# UV_Sterlizer_2.net
KiCad netlist of a schematic drawn in EAGLE
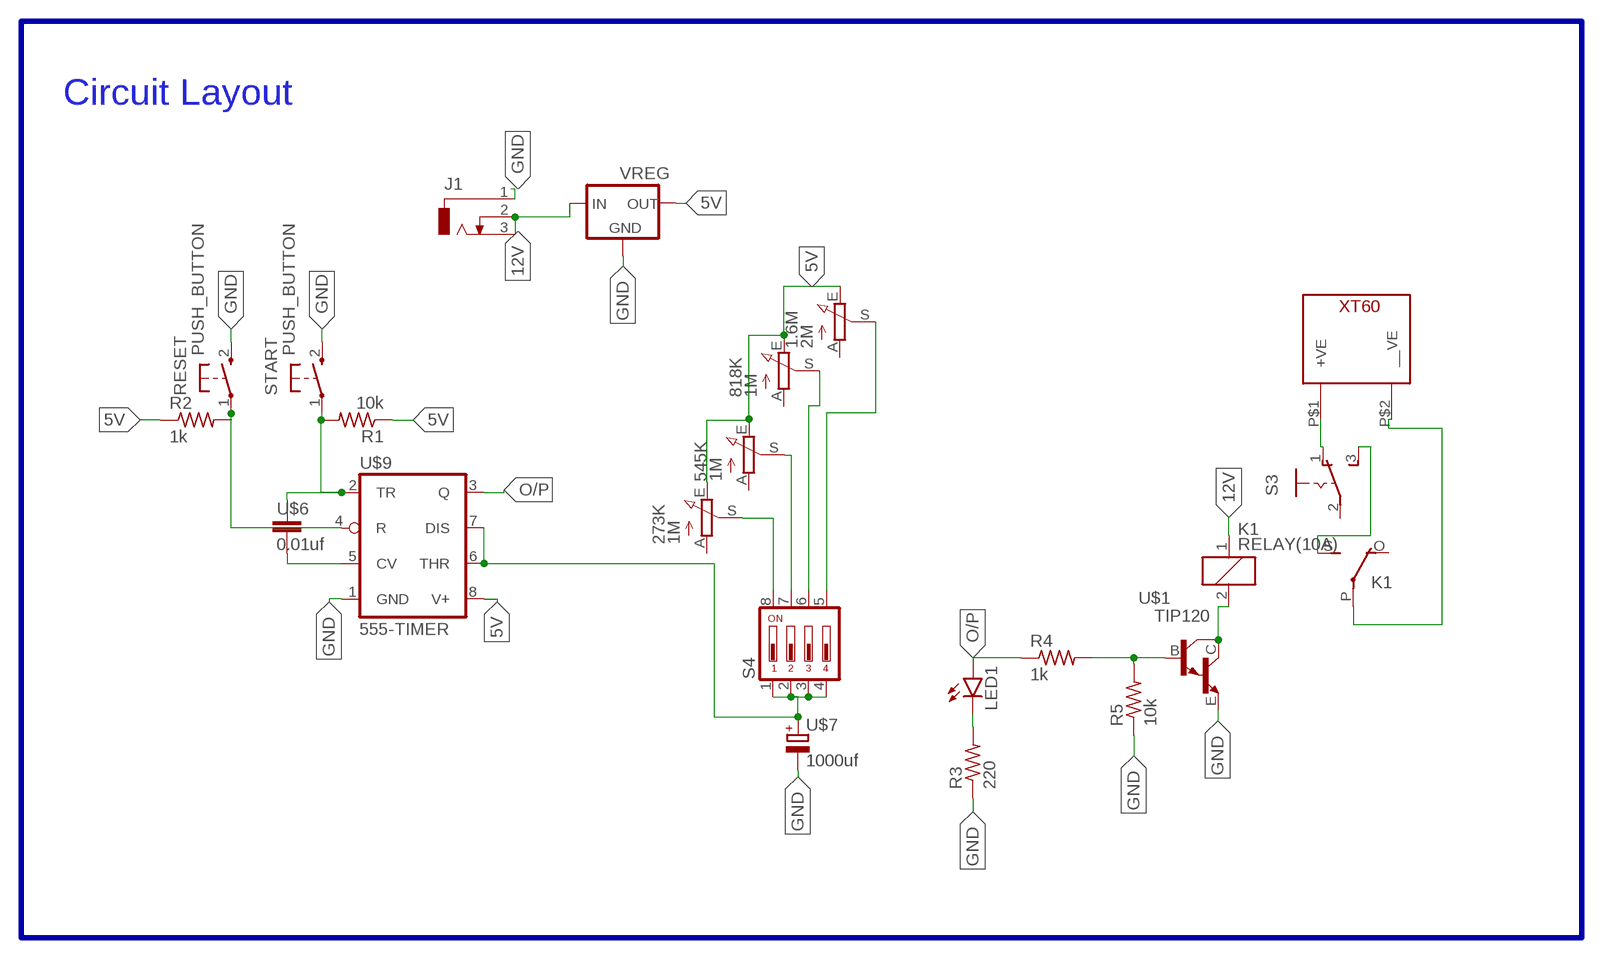
[diagram p0: schematic, sheet 1]

(export (version "E")
  (design (tool "Eeschema 10.0.6"))
  (components
    (comp (ref "1.6M")
      (value "2M")
      (footprint "eagle-import:RJ9W")
      (libsource (lib "eagle-import") (part "TRIMMER"))
    )
    (comp (ref "273K")
      (value "1M")
      (footprint "eagle-import:RJ9W")
      (libsource (lib "eagle-import") (part "TRIMMER"))
    )
    (comp (ref "545K")
      (value "1M")
      (footprint "eagle-import:RJ9W")
      (libsource (lib "eagle-import") (part "TRIMMER"))
    )
    (comp (ref "818K")
      (value "1M")
      (footprint "eagle-import:RJ9W")
      (libsource (lib "eagle-import") (part "TRIMMER"))
    )
    (comp (ref "J1")
      (value "DCJ0303")
      (footprint "eagle-import:DCJ0303")
      (libsource (lib "eagle-import") (part "DCJ0303"))
    )
    (comp (ref "K1")
      (value "RELAY(10A)")
      (footprint "eagle-import:G5LE")
      (libsource (lib "eagle-import") (part "RELAY(10A)"))
    )
    (comp (ref "LED1")
      (value "LED5MM")
      (footprint "eagle-import:LED5MM")
      (libsource (lib "eagle-import") (part "LED5MM"))
    )
    (comp (ref "R1")
      (value "10k")
      (footprint "eagle-import:0204_7")
      (libsource (lib "eagle-import") (part "R-US_0204/7"))
    )
    (comp (ref "R2")
      (value "1k")
      (footprint "eagle-import:0204_7")
      (libsource (lib "eagle-import") (part "R-US_0204/7"))
    )
    (comp (ref "R3")
      (value "220")
      (footprint "eagle-import:0204_7")
      (libsource (lib "eagle-import") (part "R-US_0204/7"))
    )
    (comp (ref "R4")
      (value "1k")
      (footprint "eagle-import:0204_7")
      (libsource (lib "eagle-import") (part "R-US_0204/7"))
    )
    (comp (ref "R5")
      (value "10k")
      (footprint "eagle-import:0204_7")
      (libsource (lib "eagle-import") (part "R-US_0204/7"))
    )
    (comp (ref "RESET")
      (value "PUSH_BUTTON")
      (footprint "eagle-import:B3F-10XX")
      (libsource (lib "eagle-import") (part "PUSH_BUTTON"))
    )
    (comp (ref "S3")
      (value "SLIDING_SWITCH")
      (footprint "eagle-import:255SB")
      (libsource (lib "eagle-import") (part "SLIDING_SWITCH"))
    )
    (comp (ref "S4")
      (value "DS04")
      (footprint "eagle-import:DS-04")
      (libsource (lib "eagle-import") (part "DS04"))
    )
    (comp (ref "START")
      (value "PUSH_BUTTON")
      (footprint "eagle-import:B3F-10XX")
      (libsource (lib "eagle-import") (part "PUSH_BUTTON"))
    )
    (comp (ref "U$1")
      (value "TIP120")
      (footprint "eagle-import:TIP120")
      (libsource (lib "eagle-import") (part "TIP120"))
    )
    (comp (ref "U$6")
      (value "0.01uf")
      (footprint "eagle-import:C025-025X050")
      (libsource (lib "eagle-import") (part "CAPACITOR"))
    )
    (comp (ref "U$7")
      (value "1000uf")
      (footprint "eagle-import:E3,5-8")
      (libsource (lib "eagle-import") (part "CAP_POL"))
    )
    (comp (ref "U$8")
      (value "XT60_CONNECTOR")
      (footprint "eagle-import:XT60")
      (libsource (lib "eagle-import") (part "XT60_CONNECTOR"))
    )
    (comp (ref "U$9")
      (value "555-TIMER")
      (footprint "eagle-import:DIL08")
      (libsource (lib "eagle-import") (part "555-TIMER"))
    )
    (comp (ref "VREG")
      (value "78XX-METAL")
      (footprint "eagle-import:TO3-79")
      (libsource (lib "eagle-import") (part "78XX-METAL"))
    )
  )
  (nets
    (net (code "1") (name "5V") (class "Default")
      (node (ref "1.6M") (pin "E") (pinfunction "E_E") (pintype "passive"))
      (node (ref "273K") (pin "E") (pinfunction "E_E") (pintype "passive"))
      (node (ref "545K") (pin "E") (pinfunction "E_E") (pintype "passive"))
      (node (ref "818K") (pin "E") (pinfunction "E_E") (pintype "passive"))
      (node (ref "R1") (pin "1") (pinfunction "1_1") (pintype "passive"))
      (node (ref "R2") (pin "1") (pinfunction "1_1") (pintype "passive"))
      (node (ref "U$9") (pin "8") (pinfunction "V+_8") (pintype "power_in"))
      (node (ref "VREG") (pin "1") (pinfunction "OUT_1") (pintype "passive"))
    )
    (net (code "2") (name "12V") (class "Default")
      (node (ref "J1") (pin "2") (pinfunction "2_2") (pintype "passive"))
      (node (ref "J1") (pin "3") (pinfunction "3_3") (pintype "passive"))
      (node (ref "K1") (pin "1") (pinfunction "1_1") (pintype "passive"))
      (node (ref "VREG") (pin "3") (pinfunction "IN_3") (pintype "input"))
    )
    (net (code "3") (name "GND") (class "Default")
      (node (ref "J1") (pin "1") (pinfunction "1_1") (pintype "passive"))
      (node (ref "R3") (pin "1") (pinfunction "1_1") (pintype "passive"))
      (node (ref "R5") (pin "1") (pinfunction "1_1") (pintype "passive"))
      (node (ref "RESET") (pin "2") (pinfunction "S_2") (pintype "passive"))
      (node (ref "START") (pin "2") (pinfunction "S_2") (pintype "passive"))
      (node (ref "U$1") (pin "E") (pinfunction "E_E") (pintype "passive"))
      (node (ref "U$7") (pin "-") (pinfunction "-_-") (pintype "passive"))
      (node (ref "U$9") (pin "1") (pinfunction "GND_1") (pintype "power_in"))
      (node (ref "VREG") (pin "2") (pinfunction "GND_2") (pintype "input"))
    )
    (net (code "4") (name "Net-(1.6M-PadS)") (class "Default")
      (node (ref "1.6M") (pin "S") (pinfunction "S_S") (pintype "passive"))
      (node (ref "S4") (pin "5") (pinfunction "5_5") (pintype "passive"))
    )
    (net (code "5") (name "Net-(273K-PadS)") (class "Default")
      (node (ref "273K") (pin "S") (pinfunction "S_S") (pintype "passive"))
      (node (ref "S4") (pin "8") (pinfunction "8_8") (pintype "passive"))
    )
    (net (code "6") (name "Net-(545K-PadS)") (class "Default")
      (node (ref "545K") (pin "S") (pinfunction "S_S") (pintype "passive"))
      (node (ref "S4") (pin "7") (pinfunction "7_7") (pintype "passive"))
    )
    (net (code "7") (name "Net-(818K-PadS)") (class "Default")
      (node (ref "818K") (pin "S") (pinfunction "S_S") (pintype "passive"))
      (node (ref "S4") (pin "6") (pinfunction "6_6") (pintype "passive"))
    )
    (net (code "8") (name "Net-(K1-Pad2)") (class "Default")
      (node (ref "K1") (pin "2") (pinfunction "2_2") (pintype "passive"))
      (node (ref "U$1") (pin "C") (pinfunction "C_C") (pintype "passive"))
    )
    (net (code "9") (name "Net-(LED1-C)") (class "Default")
      (node (ref "LED1") (pin "K") (pinfunction "C_K") (pintype "passive"))
      (node (ref "R3") (pin "2") (pinfunction "2_2") (pintype "passive"))
    )
    (net (code "10") (name "Net-(R4-Pad2)") (class "Default")
      (node (ref "R4") (pin "2") (pinfunction "2_2") (pintype "passive"))
      (node (ref "R5") (pin "2") (pinfunction "2_2") (pintype "passive"))
      (node (ref "U$1") (pin "B") (pinfunction "B_B") (pintype "passive"))
    )
    (net (code "11") (name "Net-(RESET-P)") (class "Default")
      (node (ref "R2") (pin "2") (pinfunction "2_2") (pintype "passive"))
      (node (ref "RESET") (pin "1") (pinfunction "P_1") (pintype "passive"))
      (node (ref "U$9") (pin "4") (pinfunction "R_4") (pintype "input"))
    )
    (net (code "12") (name "Net-(S3-O)") (class "Default")
      (node (ref "S3") (pin "1") (pinfunction "O_1") (pintype "passive"))
      (node (ref "U$8") (pin "P$1") (pinfunction "+VE_P$1") (pintype "bidirectional"))
    )
    (net (code "13") (name "Net-(S3-S)") (class "Default")
      (node (ref "K1") (pin "S") (pinfunction "S_S") (pintype "passive"))
      (node (ref "S3") (pin "3") (pinfunction "S_3") (pintype "passive"))
    )
    (net (code "14") (name "Net-(START-P)") (class "Default")
      (node (ref "R1") (pin "2") (pinfunction "2_2") (pintype "passive"))
      (node (ref "START") (pin "1") (pinfunction "P_1") (pintype "passive"))
      (node (ref "U$6") (pin "1") (pinfunction "1_1") (pintype "passive"))
      (node (ref "U$9") (pin "2") (pinfunction "TR_2") (pintype "input"))
    )
    (net (code "15") (name "Net-(U$8-__VE)") (class "Default")
      (node (ref "K1") (pin "P") (pinfunction "P_P") (pintype "passive"))
      (node (ref "U$8") (pin "P$2") (pinfunction "__VE_P$2") (pintype "bidirectional"))
    )
    (net (code "16") (name "Net-(U$9-CV)") (class "Default")
      (node (ref "U$6") (pin "2") (pinfunction "2_2") (pintype "passive"))
      (node (ref "U$9") (pin "5") (pinfunction "CV_5") (pintype "input"))
    )
    (net (code "17") (name "Net-(U$9-DIS)") (class "Default")
      (node (ref "S4") (pin "1") (pinfunction "1_1") (pintype "passive"))
      (node (ref "S4") (pin "2") (pinfunction "2_2") (pintype "passive"))
      (node (ref "S4") (pin "3") (pinfunction "3_3") (pintype "passive"))
      (node (ref "S4") (pin "4") (pinfunction "4_4") (pintype "passive"))
      (node (ref "U$7") (pin "+") (pinfunction "+_+") (pintype "passive"))
      (node (ref "U$9") (pin "6") (pinfunction "THR_6") (pintype "input"))
      (node (ref "U$9") (pin "7") (pinfunction "DIS_7") (pintype "input"))
    )
    (net (code "18") (name "O{slash}P") (class "Default")
      (node (ref "LED1") (pin "A") (pinfunction "A_A") (pintype "passive"))
      (node (ref "R4") (pin "1") (pinfunction "1_1") (pintype "passive"))
      (node (ref "U$9") (pin "3") (pinfunction "Q_3") (pintype "output"))
    )
    (net (code "19") (name "unconnected-(1.6M-PadA)") (class "Default")
      (node (ref "1.6M") (pin "A") (pinfunction "A_A") (pintype "passive"))
    )
    (net (code "20") (name "unconnected-(273K-PadA)") (class "Default")
      (node (ref "273K") (pin "A") (pinfunction "A_A") (pintype "passive"))
    )
    (net (code "21") (name "unconnected-(545K-PadA)") (class "Default")
      (node (ref "545K") (pin "A") (pinfunction "A_A") (pintype "passive"))
    )
    (net (code "22") (name "unconnected-(818K-PadA)") (class "Default")
      (node (ref "818K") (pin "A") (pinfunction "A_A") (pintype "passive"))
    )
    (net (code "23") (name "unconnected-(K1-PadO)") (class "Default")
      (node (ref "K1") (pin "O") (pinfunction "O_O") (pintype "passive"))
    )
    (net (code "24") (name "unconnected-(S3-P-Pad2)") (class "Default")
      (node (ref "S3") (pin "2") (pinfunction "P_2") (pintype "passive"))
    )
  )
)
